# IRduino_V1_0.net
KiCad netlist of a schematic drawn in EAGLE
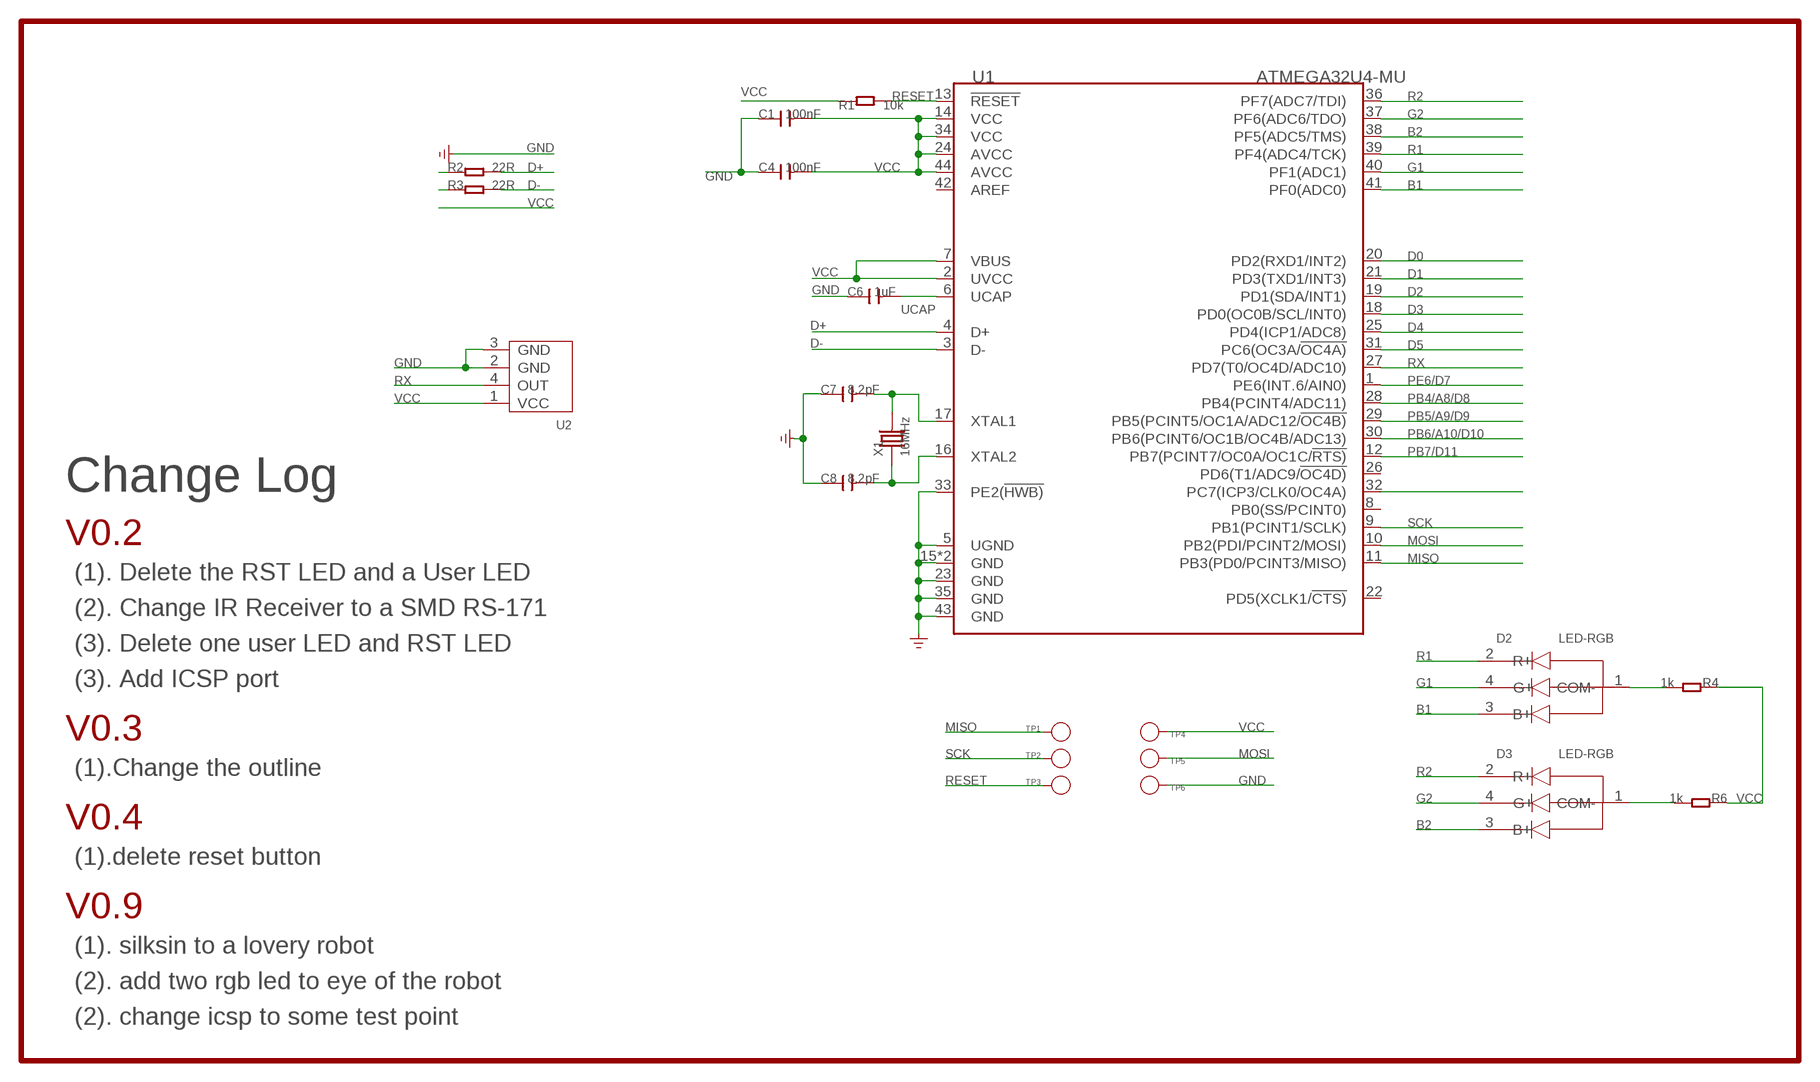
[diagram p0: schematic, sheet 1]

(export (version "E")
  (design (tool "Eeschema 10.0.6"))
  (components
    (comp (ref "C1")
      (value "100nF")
      (footprint "eagle-import:C0603")
      (libsource (lib "eagle-import") (part "C-0603"))
    )
    (comp (ref "C4")
      (value "100nF")
      (footprint "eagle-import:C0603")
      (libsource (lib "eagle-import") (part "C-0603"))
    )
    (comp (ref "C6")
      (value "1uF")
      (footprint "eagle-import:C0603")
      (libsource (lib "eagle-import") (part "C-0603"))
    )
    (comp (ref "C7")
      (value "8.2pF")
      (footprint "eagle-import:C0603")
      (libsource (lib "eagle-import") (part "C-0603"))
    )
    (comp (ref "C8")
      (value "8.2pF")
      (footprint "eagle-import:C0603")
      (libsource (lib "eagle-import") (part "C-0603"))
    )
    (comp (ref "D2")
      (value "LED-RGB")
      (footprint "eagle-import:4P-SMD-1.6X1.5")
      (libsource (lib "eagle-import") (part "LED-RGB"))
    )
    (comp (ref "D3")
      (value "LED-RGB")
      (footprint "eagle-import:4P-SMD-1.6X1.5")
      (libsource (lib "eagle-import") (part "LED-RGB"))
    )
    (comp (ref "R1")
      (value "10k")
      (footprint "eagle-import:R0603")
      (libsource (lib "eagle-import") (part "R-0603"))
    )
    (comp (ref "R2")
      (value "22R")
      (footprint "eagle-import:R0603")
      (libsource (lib "eagle-import") (part "R-0603"))
    )
    (comp (ref "R3")
      (value "22R")
      (footprint "eagle-import:R0603")
      (libsource (lib "eagle-import") (part "R-0603"))
    )
    (comp (ref "R4")
      (value "1k")
      (footprint "eagle-import:R0603")
      (libsource (lib "eagle-import") (part "R-0603"))
    )
    (comp (ref "R6")
      (value "1k")
      (footprint "eagle-import:R0603")
      (libsource (lib "eagle-import") (part "R-0603"))
    )
    (comp (ref "TP1")
      (value "PAD-TEST-POINT'3535'")
      (footprint "eagle-import:TP_3535")
      (fields (field (name "PARTNO") "DNP"))
      (libsource (lib "eagle-import") (part "PAD-TEST-POINT'3535'"))
    )
    (comp (ref "TP2")
      (value "PAD-TEST-POINT'3535'")
      (footprint "eagle-import:TP_3535")
      (fields (field (name "PARTNO") "DNP"))
      (libsource (lib "eagle-import") (part "PAD-TEST-POINT'3535'"))
    )
    (comp (ref "TP3")
      (value "PAD-TEST-POINT'3535'")
      (footprint "eagle-import:TP_3535")
      (fields (field (name "PARTNO") "DNP"))
      (libsource (lib "eagle-import") (part "PAD-TEST-POINT'3535'"))
    )
    (comp (ref "TP4")
      (value "PAD-TEST-POINT'3535'")
      (footprint "eagle-import:TP_3535")
      (fields (field (name "PARTNO") "DNP"))
      (libsource (lib "eagle-import") (part "PAD-TEST-POINT'3535'"))
    )
    (comp (ref "TP5")
      (value "PAD-TEST-POINT'3535'")
      (footprint "eagle-import:TP_3535")
      (fields (field (name "PARTNO") "DNP"))
      (libsource (lib "eagle-import") (part "PAD-TEST-POINT'3535'"))
    )
    (comp (ref "TP6")
      (value "PAD-TEST-POINT'3535'")
      (footprint "eagle-import:TP_3535")
      (fields (field (name "PARTNO") "DNP"))
      (libsource (lib "eagle-import") (part "PAD-TEST-POINT'3535'"))
    )
    (comp (ref "U1")
      (value "ATMEGA32U4-MU")
      (footprint "eagle-import:QFN44")
      (libsource (lib "eagle-import") (part "ATMEGA32U4-MU"))
    )
    (comp (ref "U2")
      (value "RS-171")
      (footprint "eagle-import:4P-SMD-L7.6_W5.75MM")
      (libsource (lib "eagle-import") (part "RS-171"))
    )
    (comp (ref "X1")
      (value "16MHz")
      (footprint "eagle-import:2P-SMD-5X3.2")
      (libsource (lib "eagle-import") (part "CRYSTAL'5032'"))
    )
  )
  (nets
    (net (code "1") (name "/B1") (class "Default")
      (node (ref "D2") (pin "3") (pinfunction "B+_3") (pintype "bidirectional"))
      (node (ref "U1") (pin "41") (pinfunction "PF0(ADC0)_41") (pintype "bidirectional"))
    )
    (net (code "2") (name "/B2") (class "Default")
      (node (ref "D3") (pin "3") (pinfunction "B+_3") (pintype "bidirectional"))
      (node (ref "U1") (pin "38") (pinfunction "PF5(ADC5/TMS)_38") (pintype "bidirectional"))
    )
    (net (code "3") (name "/D+") (class "Default")
      (node (ref "R2") (pin "2") (pinfunction "2_2") (pintype "passive"))
      (node (ref "U1") (pin "4") (pinfunction "D+_4") (pintype "bidirectional"))
    )
    (net (code "4") (name "/D-") (class "Default")
      (node (ref "R3") (pin "2") (pinfunction "2_2") (pintype "passive"))
      (node (ref "U1") (pin "3") (pinfunction "D-_3") (pintype "bidirectional"))
    )
    (net (code "5") (name "/D0") (class "Default")
      (node (ref "U1") (pin "20") (pinfunction "PD2(RXD1/INT2)_20") (pintype "bidirectional"))
    )
    (net (code "6") (name "/D1") (class "Default")
      (node (ref "U1") (pin "21") (pinfunction "PD3(TXD1/INT3)_21") (pintype "bidirectional"))
    )
    (net (code "7") (name "/D2") (class "Default")
      (node (ref "U1") (pin "19") (pinfunction "PD1(SDA/INT1)_19") (pintype "bidirectional"))
    )
    (net (code "8") (name "/D3") (class "Default")
      (node (ref "U1") (pin "18") (pinfunction "PD0(OC0B/SCL/INT0)_18") (pintype "bidirectional"))
    )
    (net (code "9") (name "/D4") (class "Default")
      (node (ref "U1") (pin "25") (pinfunction "PD4(ICP1/ADC8)_25") (pintype "bidirectional"))
    )
    (net (code "10") (name "/D5") (class "Default")
      (node (ref "U1") (pin "31") (pinfunction "PC6(OC3A/~{OC4A})_31") (pintype "bidirectional"))
    )
    (net (code "11") (name "/G1") (class "Default")
      (node (ref "D2") (pin "4") (pinfunction "G+_4") (pintype "bidirectional"))
      (node (ref "U1") (pin "40") (pinfunction "PF1(ADC1)_40") (pintype "bidirectional"))
    )
    (net (code "12") (name "/G2") (class "Default")
      (node (ref "D3") (pin "4") (pinfunction "G+_4") (pintype "bidirectional"))
      (node (ref "U1") (pin "37") (pinfunction "PF6(ADC6/TDO)_37") (pintype "bidirectional"))
    )
    (net (code "13") (name "/MISO") (class "Default")
      (node (ref "TP1") (pin "T") (pinfunction "T_T") (pintype "bidirectional"))
      (node (ref "U1") (pin "11") (pinfunction "PB3(PD0/PCINT3/MISO)_11") (pintype "bidirectional"))
    )
    (net (code "14") (name "/MOSI") (class "Default")
      (node (ref "TP5") (pin "T") (pinfunction "T_T") (pintype "bidirectional"))
      (node (ref "U1") (pin "10") (pinfunction "PB2(PDI/PCINT2/MOSI)_10") (pintype "bidirectional"))
    )
    (net (code "15") (name "/PB4{slash}A8{slash}D8") (class "Default")
      (node (ref "U1") (pin "28") (pinfunction "PB4(PCINT4/ADC11)_28") (pintype "bidirectional"))
    )
    (net (code "16") (name "/PB5{slash}A9{slash}D9") (class "Default")
      (node (ref "U1") (pin "29") (pinfunction "PB5(PCINT5/OC1A/ADC12/~{OC4B})_29") (pintype "bidirectional"))
    )
    (net (code "17") (name "/PB6{slash}A10{slash}D10") (class "Default")
      (node (ref "U1") (pin "30") (pinfunction "PB6(PCINT6/OC1B/OC4B/ADC13)_30") (pintype "bidirectional"))
    )
    (net (code "18") (name "/PB7{slash}D11") (class "Default")
      (node (ref "U1") (pin "12") (pinfunction "PB7(PCINT7/OC0A/OC1C/~{RTS})_12") (pintype "bidirectional"))
    )
    (net (code "19") (name "/PE6{slash}D7") (class "Default")
      (node (ref "U1") (pin "1") (pinfunction "PE6(INT.6/AIN0)_1") (pintype "bidirectional"))
    )
    (net (code "20") (name "/R1") (class "Default")
      (node (ref "D2") (pin "2") (pinfunction "R+_2") (pintype "bidirectional"))
      (node (ref "U1") (pin "39") (pinfunction "PF4(ADC4/TCK)_39") (pintype "bidirectional"))
    )
    (net (code "21") (name "/R2") (class "Default")
      (node (ref "D3") (pin "2") (pinfunction "R+_2") (pintype "bidirectional"))
      (node (ref "U1") (pin "36") (pinfunction "PF7(ADC7/TDI)_36") (pintype "bidirectional"))
    )
    (net (code "22") (name "/RESET") (class "Default")
      (node (ref "R1") (pin "2") (pinfunction "2_2") (pintype "passive"))
      (node (ref "TP3") (pin "T") (pinfunction "T_T") (pintype "bidirectional"))
      (node (ref "U1") (pin "13") (pinfunction "~{RESET}_13") (pintype "bidirectional"))
    )
    (net (code "23") (name "/RX") (class "Default")
      (node (ref "U1") (pin "27") (pinfunction "PD7(T0/OC4D/ADC10)_27") (pintype "bidirectional"))
      (node (ref "U2") (pin "4") (pinfunction "OUT_4") (pintype "bidirectional"))
    )
    (net (code "24") (name "/SCK") (class "Default")
      (node (ref "TP2") (pin "T") (pinfunction "T_T") (pintype "bidirectional"))
      (node (ref "U1") (pin "9") (pinfunction "PB1(PCINT1/SCLK)_9") (pintype "bidirectional"))
    )
    (net (code "25") (name "/UCAP") (class "Default")
      (node (ref "C6") (pin "2") (pinfunction "2_2") (pintype "passive"))
      (node (ref "U1") (pin "6") (pinfunction "UCAP_6") (pintype "bidirectional"))
    )
    (net (code "26") (name "/VCC") (class "Default")
      (node (ref "C1") (pin "2") (pinfunction "2_2") (pintype "passive"))
      (node (ref "C4") (pin "2") (pinfunction "2_2") (pintype "passive"))
      (node (ref "R1") (pin "1") (pinfunction "1_1") (pintype "passive"))
      (node (ref "R4") (pin "1") (pinfunction "1_1") (pintype "passive"))
      (node (ref "R6") (pin "1") (pinfunction "1_1") (pintype "passive"))
      (node (ref "TP4") (pin "T") (pinfunction "T_T") (pintype "bidirectional"))
      (node (ref "U1") (pin "14") (pinfunction "VCC_14") (pintype "bidirectional"))
      (node (ref "U1") (pin "2") (pinfunction "UVCC_2") (pintype "bidirectional"))
      (node (ref "U1") (pin "24") (pinfunction "AVCC_24") (pintype "bidirectional"))
      (node (ref "U1") (pin "34") (pinfunction "VCC_34") (pintype "bidirectional"))
      (node (ref "U1") (pin "44") (pinfunction "AVCC_44") (pintype "bidirectional"))
      (node (ref "U1") (pin "7") (pinfunction "VBUS_7") (pintype "bidirectional"))
      (node (ref "U2") (pin "1") (pinfunction "VCC_1") (pintype "bidirectional"))
    )
    (net (code "27") (name "GND_POWER") (class "Default")
      (node (ref "C1") (pin "1") (pinfunction "1_1") (pintype "passive"))
      (node (ref "C4") (pin "1") (pinfunction "1_1") (pintype "passive"))
      (node (ref "C6") (pin "1") (pinfunction "1_1") (pintype "passive"))
      (node (ref "C7") (pin "1") (pinfunction "1_1") (pintype "passive"))
      (node (ref "C8") (pin "1") (pinfunction "1_1") (pintype "passive"))
      (node (ref "TP6") (pin "T") (pinfunction "T_T") (pintype "bidirectional"))
      (node (ref "U1") (pin "15") (pinfunction "GND_15") (pintype "bidirectional"))
      (node (ref "U1") (pin "23") (pinfunction "GND_23") (pintype "bidirectional"))
      (node (ref "U1") (pin "33") (pinfunction "PE2(~{HWB})_33") (pintype "bidirectional"))
      (node (ref "U1") (pin "35") (pinfunction "GND_35") (pintype "bidirectional"))
      (node (ref "U1") (pin "43") (pinfunction "GND_43") (pintype "bidirectional"))
      (node (ref "U1") (pin "5") (pinfunction "UGND_5") (pintype "bidirectional"))
      (node (ref "U1") (pin "TAB") (pinfunction "GND_TAB") (pintype "bidirectional"))
      (node (ref "U2") (pin "2") (pinfunction "GND_2") (pintype "bidirectional"))
      (node (ref "U2") (pin "3") (pinfunction "GND_3") (pintype "bidirectional"))
    )
    (net (code "28") (name "Net-(D2-COM-)") (class "Default")
      (node (ref "D2") (pin "1") (pinfunction "COM-_1") (pintype "bidirectional"))
      (node (ref "R4") (pin "2") (pinfunction "2_2") (pintype "passive"))
    )
    (net (code "29") (name "Net-(D3-COM-)") (class "Default")
      (node (ref "D3") (pin "1") (pinfunction "COM-_1") (pintype "bidirectional"))
      (node (ref "R6") (pin "2") (pinfunction "2_2") (pintype "passive"))
    )
    (net (code "30") (name "Net-(U1-XTAL1)") (class "Default")
      (node (ref "C7") (pin "2") (pinfunction "2_2") (pintype "passive"))
      (node (ref "U1") (pin "17") (pinfunction "XTAL1_17") (pintype "bidirectional"))
      (node (ref "X1") (pin "2") (pinfunction "2_2") (pintype "passive"))
    )
    (net (code "31") (name "Net-(U1-XTAL2)") (class "Default")
      (node (ref "C8") (pin "2") (pinfunction "2_2") (pintype "passive"))
      (node (ref "U1") (pin "16") (pinfunction "XTAL2_16") (pintype "bidirectional"))
      (node (ref "X1") (pin "1") (pinfunction "1_1") (pintype "passive"))
    )
    (net (code "32") (name "unconnected-(R2-Pad1)") (class "Default")
      (node (ref "R2") (pin "1") (pinfunction "1_1") (pintype "passive"))
    )
    (net (code "33") (name "unconnected-(R3-Pad1)") (class "Default")
      (node (ref "R3") (pin "1") (pinfunction "1_1") (pintype "passive"))
    )
    (net (code "34") (name "unconnected-(U1-AREF-Pad42)") (class "Default")
      (node (ref "U1") (pin "42") (pinfunction "AREF_42") (pintype "bidirectional"))
    )
    (net (code "35") (name "unconnected-(U1-PB0(SS{slash}PCINT0)-Pad8)") (class "Default")
      (node (ref "U1") (pin "8") (pinfunction "PB0(SS/PCINT0)_8") (pintype "bidirectional"))
    )
    (net (code "36") (name "unconnected-(U1-PC7(ICP3{slash}CLK0{slash}OC4A)-Pad32)") (class "Default")
      (node (ref "U1") (pin "32") (pinfunction "PC7(ICP3/CLK0/OC4A)_32") (pintype "bidirectional"))
    )
    (net (code "37") (name "unconnected-(U1-PD5(XCLK1{slash}~{CTS})-Pad22)") (class "Default")
      (node (ref "U1") (pin "22") (pinfunction "PD5(XCLK1/~{CTS})_22") (pintype "bidirectional"))
    )
    (net (code "38") (name "unconnected-(U1-PD6(T1{slash}ADC9{slash}~{OC4D})-Pad26)") (class "Default")
      (node (ref "U1") (pin "26") (pinfunction "PD6(T1/ADC9/~{OC4D})_26") (pintype "bidirectional"))
    )
  )
)
